# lm3410-sepic-rgb-led-driver-22mm-mk-1.net
KiCad netlist of a schematic drawn in EAGLE
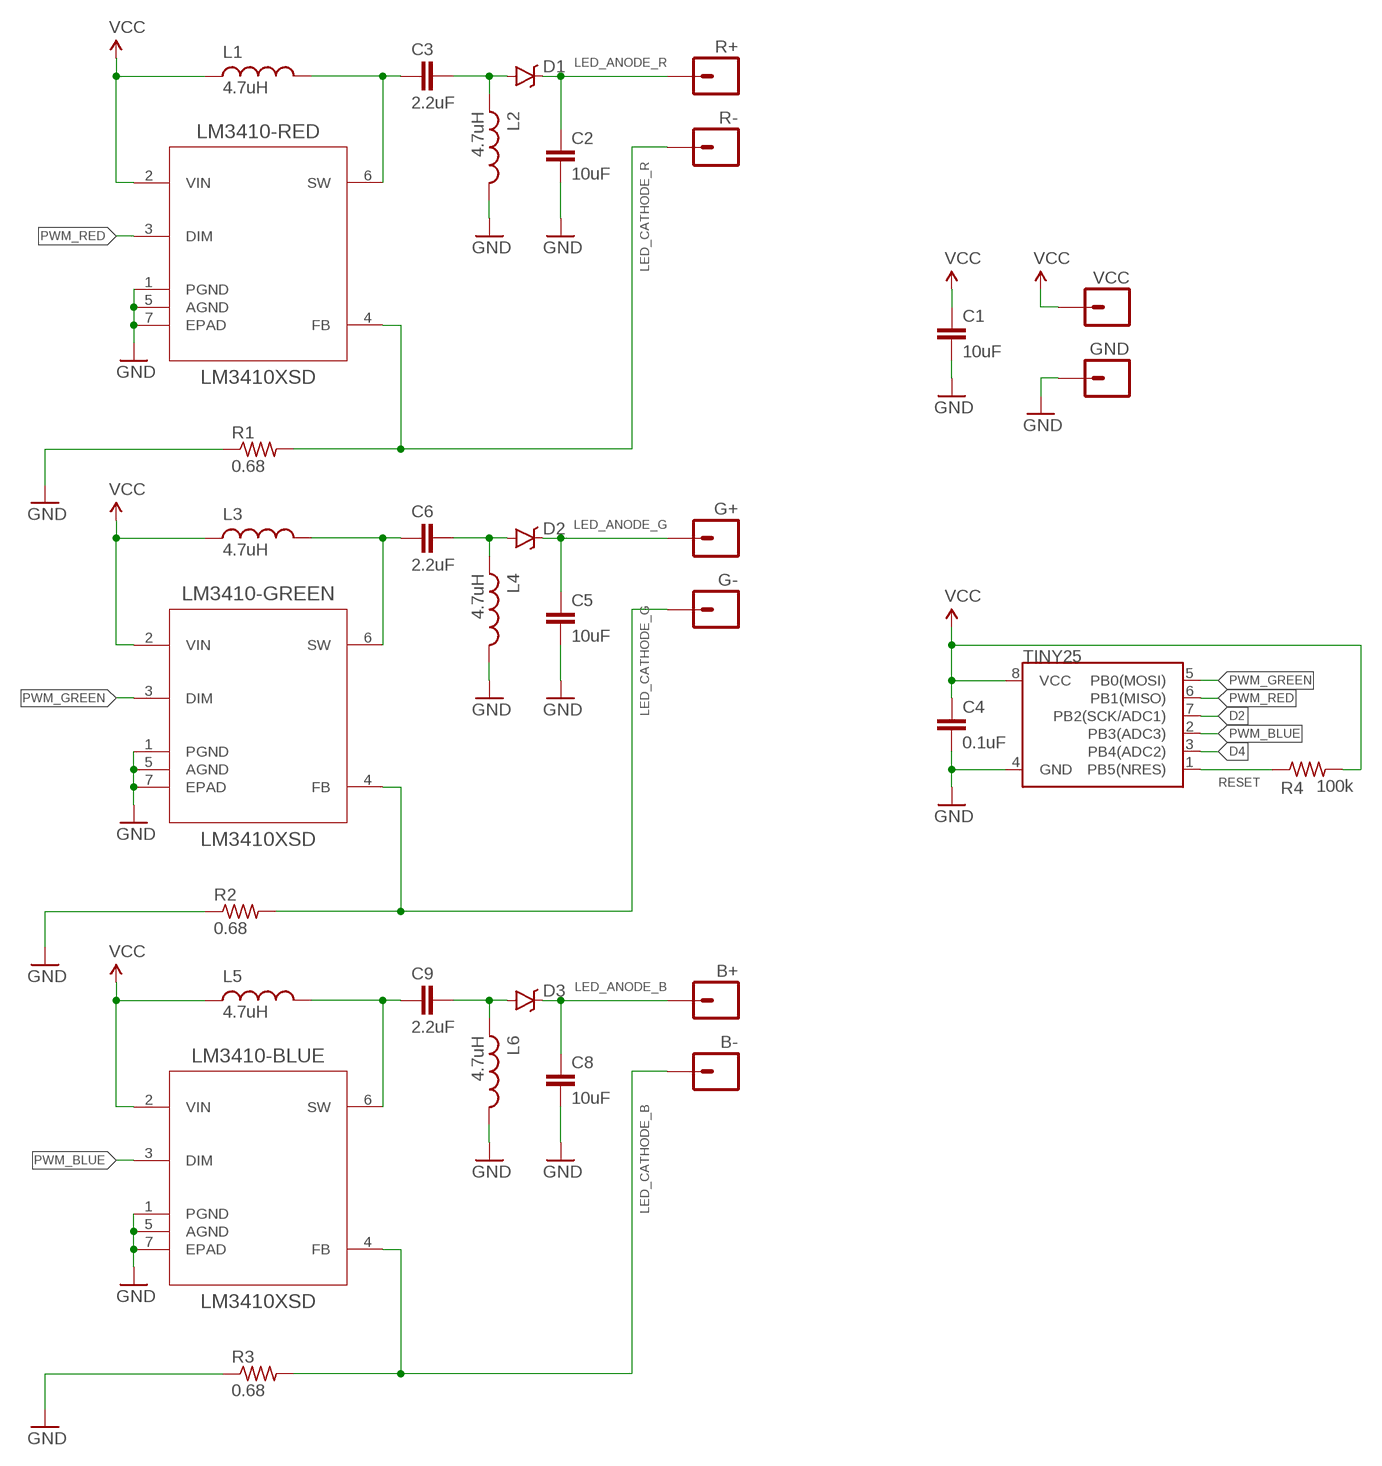
[diagram p0: schematic, sheet 1]

(export (version "E")
  (design (tool "Eeschema 10.0.6"))
  (components
    (comp (ref "B+")
      (value "M01SMD_ANCHOR")
      (footprint "eagle-import:1X01_SMD_ANCHOR")
      (libsource (lib "eagle-import") (part "M01SMD_ANCHOR"))
    )
    (comp (ref "B-")
      (value "M01SMD_ANCHOR")
      (footprint "eagle-import:1X01_SMD_ANCHOR")
      (libsource (lib "eagle-import") (part "M01SMD_ANCHOR"))
    )
    (comp (ref "C1")
      (value "10uF")
      (footprint "eagle-import:C0603")
      (libsource (lib "eagle-import") (part "CAPACITOR-CERAMICC0603"))
    )
    (comp (ref "C2")
      (value "10uF")
      (footprint "eagle-import:C0603")
      (libsource (lib "eagle-import") (part "CAPACITOR-CERAMICC0603"))
    )
    (comp (ref "C3")
      (value "2.2uF")
      (footprint "eagle-import:C0603")
      (libsource (lib "eagle-import") (part "CAPACITOR-CERAMICC0603"))
    )
    (comp (ref "C4")
      (value "0.1uF")
      (footprint "eagle-import:C0402")
      (libsource (lib "eagle-import") (part "CAPACITOR-CERAMICC0402"))
    )
    (comp (ref "C5")
      (value "10uF")
      (footprint "eagle-import:C0603")
      (libsource (lib "eagle-import") (part "CAPACITOR-CERAMICC0603"))
    )
    (comp (ref "C6")
      (value "2.2uF")
      (footprint "eagle-import:C0603")
      (libsource (lib "eagle-import") (part "CAPACITOR-CERAMICC0603"))
    )
    (comp (ref "C8")
      (value "10uF")
      (footprint "eagle-import:C0603")
      (libsource (lib "eagle-import") (part "CAPACITOR-CERAMICC0603"))
    )
    (comp (ref "C9")
      (value "2.2uF")
      (footprint "eagle-import:C0603")
      (libsource (lib "eagle-import") (part "CAPACITOR-CERAMICC0603"))
    )
    (comp (ref "D1")
      (value "PMEG4005EJ")
      (footprint "eagle-import:SOD-323")
      (libsource (lib "eagle-import") (part "DIODE-SCHOTTKY-PMEG4005EJ"))
    )
    (comp (ref "D2")
      (value "PMEG4005EJ")
      (footprint "eagle-import:SOD-323")
      (libsource (lib "eagle-import") (part "DIODE-SCHOTTKY-PMEG4005EJ"))
    )
    (comp (ref "D3")
      (value "PMEG4005EJ")
      (footprint "eagle-import:SOD-323")
      (libsource (lib "eagle-import") (part "DIODE-SCHOTTKY-PMEG4005EJ"))
    )
    (comp (ref "G+")
      (value "M01SMD_ANCHOR")
      (footprint "eagle-import:1X01_SMD_ANCHOR")
      (libsource (lib "eagle-import") (part "M01SMD_ANCHOR"))
    )
    (comp (ref "G-")
      (value "M01SMD_ANCHOR")
      (footprint "eagle-import:1X01_SMD_ANCHOR")
      (libsource (lib "eagle-import") (part "M01SMD_ANCHOR"))
    )
    (comp (ref "GND")
      (value "M01NOT-A-VIA-NOPE")
      (footprint "eagle-import:1X01_NOSILK_NOSTOP")
      (libsource (lib "eagle-import") (part "M01NOT-A-VIA-NOPE"))
    )
    (comp (ref "L1")
      (value "4.7uH")
      (footprint "eagle-import:INDUCTOR_2X1.6MM")
      (libsource (lib "eagle-import") (part "INDUCTORIFSC-0806"))
    )
    (comp (ref "L2")
      (value "4.7uH")
      (footprint "eagle-import:INDUCTOR_2X1.6MM")
      (libsource (lib "eagle-import") (part "INDUCTORIFSC-0806"))
    )
    (comp (ref "L3")
      (value "4.7uH")
      (footprint "eagle-import:INDUCTOR_2X1.6MM")
      (libsource (lib "eagle-import") (part "INDUCTORIFSC-0806"))
    )
    (comp (ref "L4")
      (value "4.7uH")
      (footprint "eagle-import:INDUCTOR_2X1.6MM")
      (libsource (lib "eagle-import") (part "INDUCTORIFSC-0806"))
    )
    (comp (ref "L5")
      (value "4.7uH")
      (footprint "eagle-import:INDUCTOR_2X1.6MM")
      (libsource (lib "eagle-import") (part "INDUCTORIFSC-0806"))
    )
    (comp (ref "L6")
      (value "4.7uH")
      (footprint "eagle-import:INDUCTOR_2X1.6MM")
      (libsource (lib "eagle-import") (part "INDUCTORIFSC-0806"))
    )
    (comp (ref "LM3410-BLUE")
      (value "LM3410XSD")
      (footprint "eagle-import:DFN300X300X80-7N")
      (libsource (lib "eagle-import") (part "LM3410XSD"))
    )
    (comp (ref "LM3410-GREEN")
      (value "LM3410XSD")
      (footprint "eagle-import:DFN300X300X80-7N")
      (libsource (lib "eagle-import") (part "LM3410XSD"))
    )
    (comp (ref "LM3410-RED")
      (value "LM3410XSD")
      (footprint "eagle-import:DFN300X300X80-7N")
      (libsource (lib "eagle-import") (part "LM3410XSD"))
    )
    (comp (ref "R+")
      (value "M01SMD_ANCHOR")
      (footprint "eagle-import:1X01_SMD_ANCHOR")
      (libsource (lib "eagle-import") (part "M01SMD_ANCHOR"))
    )
    (comp (ref "R-")
      (value "M01SMD_ANCHOR")
      (footprint "eagle-import:1X01_SMD_ANCHOR")
      (libsource (lib "eagle-import") (part "M01SMD_ANCHOR"))
    )
    (comp (ref "R1")
      (value "0.68")
      (footprint "eagle-import:R0805")
      (libsource (lib "eagle-import") (part "RESISTORR0805"))
    )
    (comp (ref "R2")
      (value "0.68")
      (footprint "eagle-import:R0805")
      (libsource (lib "eagle-import") (part "RESISTORR0805"))
    )
    (comp (ref "R3")
      (value "0.68")
      (footprint "eagle-import:R0805")
      (libsource (lib "eagle-import") (part "RESISTORR0805"))
    )
    (comp (ref "R4")
      (value "100k")
      (footprint "eagle-import:R0402")
      (libsource (lib "eagle-import") (part "RESISTORR0402"))
    )
    (comp (ref "TINY25")
      (value "ATTINY45TINY25-20-SOICN")
      (footprint "eagle-import:SO08")
      (libsource (lib "eagle-import") (part "ATTINY45TINY25-20-SOICN"))
    )
    (comp (ref "VCC")
      (value "M01NOT-A-VIA-NOPE")
      (footprint "eagle-import:1X01_NOSILK_NOSTOP")
      (libsource (lib "eagle-import") (part "M01NOT-A-VIA-NOPE"))
    )
  )
  (nets
    (net (code "1") (name "/LED_ANODE_B") (class "Default")
      (node (ref "B+") (pin "P$1") (pinfunction "1_P$1") (pintype "passive"))
      (node (ref "C8") (pin "1") (pinfunction "1_1") (pintype "passive"))
      (node (ref "D3") (pin "C") (pinfunction "C_C") (pintype "passive"))
    )
    (net (code "2") (name "/LED_ANODE_G") (class "Default")
      (node (ref "C5") (pin "1") (pinfunction "1_1") (pintype "passive"))
      (node (ref "D2") (pin "C") (pinfunction "C_C") (pintype "passive"))
      (node (ref "G+") (pin "P$1") (pinfunction "1_P$1") (pintype "passive"))
    )
    (net (code "3") (name "/LED_ANODE_R") (class "Default")
      (node (ref "C2") (pin "1") (pinfunction "1_1") (pintype "passive"))
      (node (ref "D1") (pin "C") (pinfunction "C_C") (pintype "passive"))
      (node (ref "R+") (pin "P$1") (pinfunction "1_P$1") (pintype "passive"))
    )
    (net (code "4") (name "/LED_CATHODE_B") (class "Default")
      (node (ref "B-") (pin "P$1") (pinfunction "1_P$1") (pintype "passive"))
      (node (ref "LM3410-BLUE") (pin "4") (pinfunction "FB_4") (pintype "input"))
      (node (ref "R3") (pin "2") (pinfunction "2_2") (pintype "passive"))
    )
    (net (code "5") (name "/LED_CATHODE_G") (class "Default")
      (node (ref "G-") (pin "P$1") (pinfunction "1_P$1") (pintype "passive"))
      (node (ref "LM3410-GREEN") (pin "4") (pinfunction "FB_4") (pintype "input"))
      (node (ref "R2") (pin "2") (pinfunction "2_2") (pintype "passive"))
    )
    (net (code "6") (name "/LED_CATHODE_R") (class "Default")
      (node (ref "LM3410-RED") (pin "4") (pinfunction "FB_4") (pintype "input"))
      (node (ref "R-") (pin "P$1") (pinfunction "1_P$1") (pintype "passive"))
      (node (ref "R1") (pin "2") (pinfunction "2_2") (pintype "passive"))
    )
    (net (code "7") (name "/RESET") (class "Default")
      (node (ref "R4") (pin "1") (pinfunction "1_1") (pintype "passive"))
      (node (ref "TINY25") (pin "1") (pinfunction "PB5(NRES)_1") (pintype "bidirectional"))
    )
    (net (code "8") (name "D2") (class "Default")
      (node (ref "TINY25") (pin "7") (pinfunction "PB2(SCK/ADC1)_7") (pintype "bidirectional"))
    )
    (net (code "9") (name "D4") (class "Default")
      (node (ref "TINY25") (pin "3") (pinfunction "PB4(ADC2)_3") (pintype "bidirectional"))
    )
    (net (code "10") (name "GND") (class "Default")
      (node (ref "C1") (pin "2") (pinfunction "2_2") (pintype "passive"))
      (node (ref "C2") (pin "2") (pinfunction "2_2") (pintype "passive"))
      (node (ref "C4") (pin "2") (pinfunction "2_2") (pintype "passive"))
      (node (ref "C5") (pin "2") (pinfunction "2_2") (pintype "passive"))
      (node (ref "C8") (pin "2") (pinfunction "2_2") (pintype "passive"))
      (node (ref "GND") (pin "P$1") (pinfunction "1_P$1") (pintype "passive"))
      (node (ref "L2") (pin "P$2") (pinfunction "2_P$2") (pintype "passive"))
      (node (ref "L4") (pin "P$2") (pinfunction "2_P$2") (pintype "passive"))
      (node (ref "L6") (pin "P$2") (pinfunction "2_P$2") (pintype "passive"))
      (node (ref "LM3410-BLUE") (pin "1") (pinfunction "PGND_1") (pintype "passive"))
      (node (ref "LM3410-BLUE") (pin "5") (pinfunction "AGND_5") (pintype "passive"))
      (node (ref "LM3410-BLUE") (pin "7") (pinfunction "EPAD_7") (pintype "passive"))
      (node (ref "LM3410-GREEN") (pin "1") (pinfunction "PGND_1") (pintype "passive"))
      (node (ref "LM3410-GREEN") (pin "5") (pinfunction "AGND_5") (pintype "passive"))
      (node (ref "LM3410-GREEN") (pin "7") (pinfunction "EPAD_7") (pintype "passive"))
      (node (ref "LM3410-RED") (pin "1") (pinfunction "PGND_1") (pintype "passive"))
      (node (ref "LM3410-RED") (pin "5") (pinfunction "AGND_5") (pintype "passive"))
      (node (ref "LM3410-RED") (pin "7") (pinfunction "EPAD_7") (pintype "passive"))
      (node (ref "R1") (pin "1") (pinfunction "1_1") (pintype "passive"))
      (node (ref "R2") (pin "1") (pinfunction "1_1") (pintype "passive"))
      (node (ref "R3") (pin "1") (pinfunction "1_1") (pintype "passive"))
      (node (ref "TINY25") (pin "4") (pinfunction "GND_4") (pintype "bidirectional"))
    )
    (net (code "11") (name "Net-(L1-2)") (class "Default")
      (node (ref "C3") (pin "1") (pinfunction "1_1") (pintype "passive"))
      (node (ref "L1") (pin "P$2") (pinfunction "2_P$2") (pintype "passive"))
      (node (ref "LM3410-RED") (pin "6") (pinfunction "SW_6") (pintype "output"))
    )
    (net (code "12") (name "Net-(L2-1)") (class "Default")
      (node (ref "C3") (pin "2") (pinfunction "2_2") (pintype "passive"))
      (node (ref "D1") (pin "A") (pinfunction "A_A") (pintype "passive"))
      (node (ref "L2") (pin "P$1") (pinfunction "1_P$1") (pintype "passive"))
    )
    (net (code "13") (name "Net-(L3-2)") (class "Default")
      (node (ref "C6") (pin "1") (pinfunction "1_1") (pintype "passive"))
      (node (ref "L3") (pin "P$2") (pinfunction "2_P$2") (pintype "passive"))
      (node (ref "LM3410-GREEN") (pin "6") (pinfunction "SW_6") (pintype "output"))
    )
    (net (code "14") (name "Net-(L4-1)") (class "Default")
      (node (ref "C6") (pin "2") (pinfunction "2_2") (pintype "passive"))
      (node (ref "D2") (pin "A") (pinfunction "A_A") (pintype "passive"))
      (node (ref "L4") (pin "P$1") (pinfunction "1_P$1") (pintype "passive"))
    )
    (net (code "15") (name "Net-(L5-2)") (class "Default")
      (node (ref "C9") (pin "1") (pinfunction "1_1") (pintype "passive"))
      (node (ref "L5") (pin "P$2") (pinfunction "2_P$2") (pintype "passive"))
      (node (ref "LM3410-BLUE") (pin "6") (pinfunction "SW_6") (pintype "output"))
    )
    (net (code "16") (name "Net-(L6-1)") (class "Default")
      (node (ref "C9") (pin "2") (pinfunction "2_2") (pintype "passive"))
      (node (ref "D3") (pin "A") (pinfunction "A_A") (pintype "passive"))
      (node (ref "L6") (pin "P$1") (pinfunction "1_P$1") (pintype "passive"))
    )
    (net (code "17") (name "PWM_BLUE") (class "Default")
      (node (ref "LM3410-BLUE") (pin "3") (pinfunction "DIM_3") (pintype "input"))
      (node (ref "TINY25") (pin "2") (pinfunction "PB3(ADC3)_2") (pintype "bidirectional"))
    )
    (net (code "18") (name "PWM_GREEN") (class "Default")
      (node (ref "LM3410-GREEN") (pin "3") (pinfunction "DIM_3") (pintype "input"))
      (node (ref "TINY25") (pin "5") (pinfunction "PB0(MOSI)_5") (pintype "bidirectional"))
    )
    (net (code "19") (name "PWM_RED") (class "Default")
      (node (ref "LM3410-RED") (pin "3") (pinfunction "DIM_3") (pintype "input"))
      (node (ref "TINY25") (pin "6") (pinfunction "PB1(MISO)_6") (pintype "bidirectional"))
    )
    (net (code "20") (name "VCC") (class "Default")
      (node (ref "C1") (pin "1") (pinfunction "1_1") (pintype "passive"))
      (node (ref "C4") (pin "1") (pinfunction "1_1") (pintype "passive"))
      (node (ref "L1") (pin "P$1") (pinfunction "1_P$1") (pintype "passive"))
      (node (ref "L3") (pin "P$1") (pinfunction "1_P$1") (pintype "passive"))
      (node (ref "L5") (pin "P$1") (pinfunction "1_P$1") (pintype "passive"))
      (node (ref "LM3410-BLUE") (pin "2") (pinfunction "VIN_2") (pintype "power_in"))
      (node (ref "LM3410-GREEN") (pin "2") (pinfunction "VIN_2") (pintype "power_in"))
      (node (ref "LM3410-RED") (pin "2") (pinfunction "VIN_2") (pintype "power_in"))
      (node (ref "R4") (pin "2") (pinfunction "2_2") (pintype "passive"))
      (node (ref "TINY25") (pin "8") (pinfunction "VCC_8") (pintype "bidirectional"))
      (node (ref "VCC") (pin "P$1") (pinfunction "1_P$1") (pintype "passive"))
    )
  )
)
